# Zio_OLED_Display.net
KiCad netlist of a schematic drawn in EAGLE
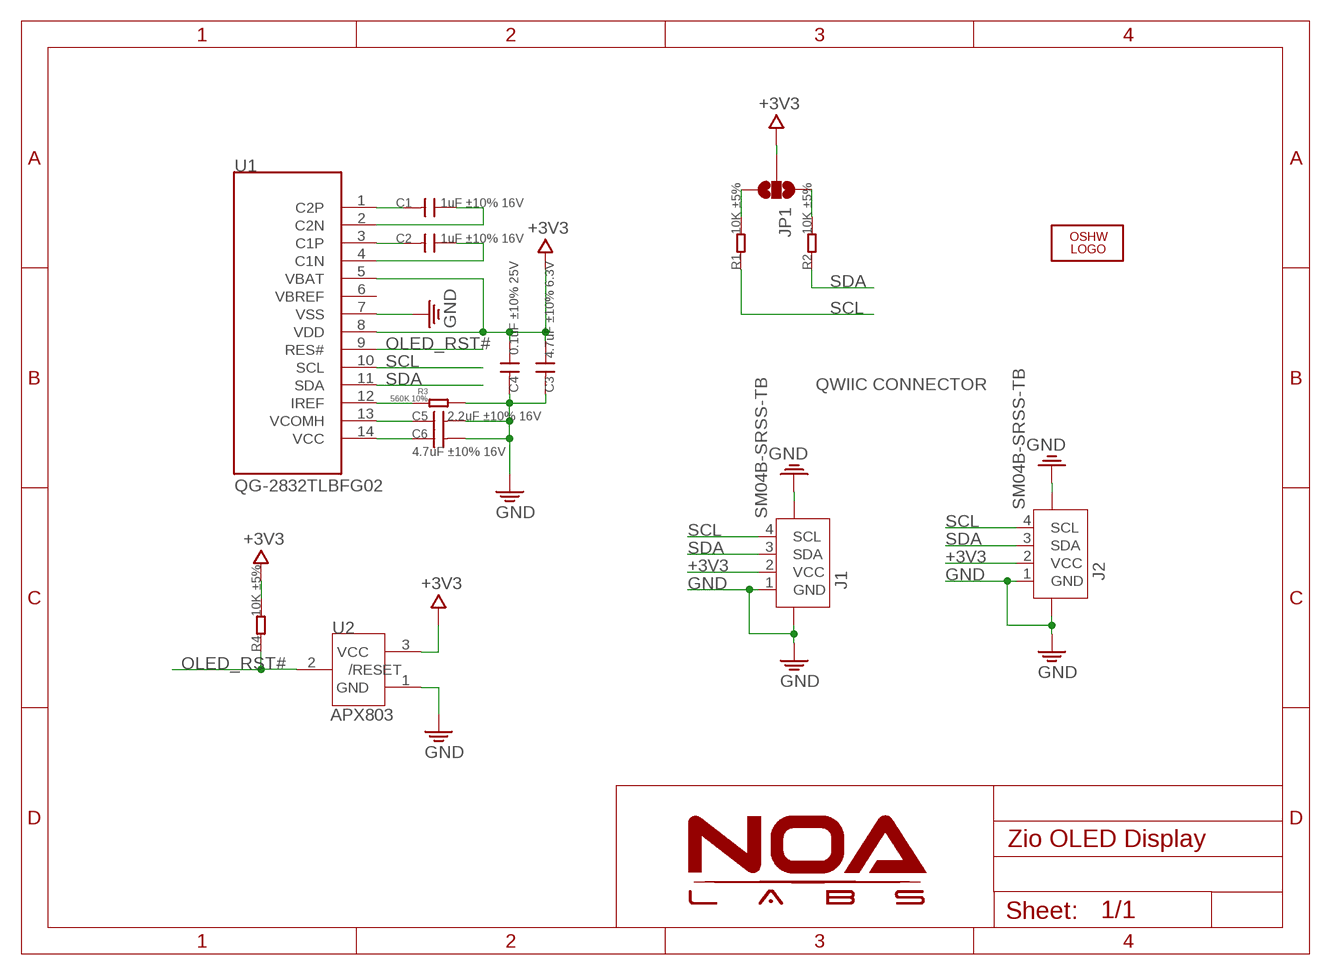
[diagram p0: schematic, sheet 1]

(export (version "E")
  (design (tool "Eeschema 10.0.6"))
  (components
    (comp (ref "C1")
      (value "1uF ±10% 16V")
      (footprint "eagle-import:0603")
      (libsource (lib "eagle-import") (part "C-0603"))
    )
    (comp (ref "C2")
      (value "1uF ±10% 16V")
      (footprint "eagle-import:0603")
      (libsource (lib "eagle-import") (part "C-0603"))
    )
    (comp (ref "C3")
      (value "4.7uF ±10% 6.3V")
      (footprint "eagle-import:0603")
      (libsource (lib "eagle-import") (part "C-0603"))
    )
    (comp (ref "C4")
      (value "0.1uF ±10% 25V")
      (footprint "eagle-import:0603")
      (libsource (lib "eagle-import") (part "C-0603"))
    )
    (comp (ref "C5")
      (value "2.2uF ±10% 16V")
      (footprint "eagle-import:0603")
      (libsource (lib "eagle-import") (part "C-0603"))
    )
    (comp (ref "C6")
      (value "4.7uF ±10% 16V")
      (footprint "eagle-import:0603")
      (libsource (lib "eagle-import") (part "C-0603"))
    )
    (comp (ref "J1")
      (value "SM04B-SRSS-TB")
      (footprint "eagle-import:JST-SH-4P")
      (libsource (lib "eagle-import") (part "JST-SH-4P-1.0"))
    )
    (comp (ref "J2")
      (value "SM04B-SRSS-TB")
      (footprint "eagle-import:JST-SH-4P")
      (libsource (lib "eagle-import") (part "JST-SH-4P-1.0"))
    )
    (comp (ref "JP1")
      (value "JUMPER-SMT_3_2-NC_PASTE_NOCREM")
      (footprint "eagle-import:SMT-JUMPER_3_2-NC_PASTE_SILK_NOCREM")
      (libsource (lib "eagle-import") (part "JUMPER-SMT_3_2-NC_PASTE_NOCREM"))
    )
    (comp (ref "LOGO1")
      (value "LOGO-OSHW-6MILX0070-NT")
      (footprint "eagle-import:OSHW_6X70_NOTEXT")
      (libsource (lib "eagle-import") (part "LOGO-OSHW-6MILX0070-NT"))
    )
    (comp (ref "R1")
      (value "10K ±5%")
      (footprint "eagle-import:0603")
      (libsource (lib "eagle-import") (part "R-0603"))
    )
    (comp (ref "R2")
      (value "10K ±5%")
      (footprint "eagle-import:0603")
      (libsource (lib "eagle-import") (part "R-0603"))
    )
    (comp (ref "R3")
      (value "560K 10%")
      (footprint "eagle-import:0603")
      (libsource (lib "eagle-import") (part "R-0603"))
    )
    (comp (ref "R4")
      (value "10K ±5%")
      (footprint "eagle-import:0603")
      (libsource (lib "eagle-import") (part "R-0603"))
    )
    (comp (ref "U1")
      (value "QG-2832TLBFG02")
      (footprint "eagle-import:OLED-12832")
      (libsource (lib "eagle-import") (part "OLED-12832"))
    )
    (comp (ref "U2")
      (value "APX803")
      (footprint "eagle-import:SOT23")
      (libsource (lib "eagle-import") (part "APX803"))
    )
  )
  (nets
    (net (code "1") (name "+3V3") (class "Default")
      (node (ref "C3") (pin "1") (pinfunction "1_1") (pintype "passive"))
      (node (ref "C4") (pin "1") (pinfunction "1_1") (pintype "passive"))
      (node (ref "J1") (pin "2") (pinfunction "VCC_2") (pintype "bidirectional"))
      (node (ref "J2") (pin "2") (pinfunction "VCC_2") (pintype "bidirectional"))
      (node (ref "JP1") (pin "2") (pinfunction "2_2") (pintype "passive"))
      (node (ref "R4") (pin "2") (pinfunction "2_2") (pintype "passive"))
      (node (ref "U1") (pin "5") (pinfunction "VBAT_5") (pintype "bidirectional"))
      (node (ref "U1") (pin "8") (pinfunction "VDD_8") (pintype "bidirectional"))
      (node (ref "U2") (pin "3") (pinfunction "VCC_3") (pintype "bidirectional"))
    )
    (net (code "2") (name "/OLED_RST#") (class "Default")
      (node (ref "R4") (pin "1") (pinfunction "1_1") (pintype "passive"))
      (node (ref "U1") (pin "9") (pinfunction "RES#_9") (pintype "bidirectional"))
      (node (ref "U2") (pin "2") (pinfunction "/RESET_2") (pintype "bidirectional"))
    )
    (net (code "3") (name "/SCL") (class "Default")
      (node (ref "J1") (pin "4") (pinfunction "SCL_4") (pintype "bidirectional"))
      (node (ref "J2") (pin "4") (pinfunction "SCL_4") (pintype "bidirectional"))
      (node (ref "R1") (pin "1") (pinfunction "1_1") (pintype "passive"))
      (node (ref "U1") (pin "10") (pinfunction "SCL_10") (pintype "bidirectional"))
    )
    (net (code "4") (name "/SDA") (class "Default")
      (node (ref "J1") (pin "3") (pinfunction "SDA_3") (pintype "bidirectional"))
      (node (ref "J2") (pin "3") (pinfunction "SDA_3") (pintype "bidirectional"))
      (node (ref "R2") (pin "1") (pinfunction "1_1") (pintype "passive"))
      (node (ref "U1") (pin "11") (pinfunction "SDA_11") (pintype "bidirectional"))
    )
    (net (code "5") (name "GND") (class "Default")
      (node (ref "C3") (pin "2") (pinfunction "2_2") (pintype "passive"))
      (node (ref "C4") (pin "2") (pinfunction "2_2") (pintype "passive"))
      (node (ref "C5") (pin "2") (pinfunction "2_2") (pintype "passive"))
      (node (ref "C6") (pin "2") (pinfunction "2_2") (pintype "passive"))
      (node (ref "J1") (pin "1") (pinfunction "GND_1") (pintype "bidirectional"))
      (node (ref "J1") (pin "NC1") (pinfunction "5_NC1") (pintype "bidirectional"))
      (node (ref "J1") (pin "NC2") (pinfunction "6_NC2") (pintype "bidirectional"))
      (node (ref "J2") (pin "1") (pinfunction "GND_1") (pintype "bidirectional"))
      (node (ref "J2") (pin "NC1") (pinfunction "5_NC1") (pintype "bidirectional"))
      (node (ref "J2") (pin "NC2") (pinfunction "6_NC2") (pintype "bidirectional"))
      (node (ref "R3") (pin "1") (pinfunction "1_1") (pintype "passive"))
      (node (ref "U1") (pin "7") (pinfunction "VSS_7") (pintype "bidirectional"))
      (node (ref "U2") (pin "1") (pinfunction "GND_1") (pintype "bidirectional"))
    )
    (net (code "6") (name "Net-(JP1-Pad1)") (class "Default")
      (node (ref "JP1") (pin "1") (pinfunction "1_1") (pintype "passive"))
      (node (ref "R2") (pin "2") (pinfunction "2_2") (pintype "passive"))
    )
    (net (code "7") (name "Net-(JP1-Pad3)") (class "Default")
      (node (ref "JP1") (pin "3") (pinfunction "3_3") (pintype "passive"))
      (node (ref "R1") (pin "2") (pinfunction "2_2") (pintype "passive"))
    )
    (net (code "8") (name "Net-(U1-C1N)") (class "Default")
      (node (ref "C2") (pin "1") (pinfunction "1_1") (pintype "passive"))
      (node (ref "U1") (pin "4") (pinfunction "C1N_4") (pintype "bidirectional"))
    )
    (net (code "9") (name "Net-(U1-C1P)") (class "Default")
      (node (ref "C2") (pin "2") (pinfunction "2_2") (pintype "passive"))
      (node (ref "U1") (pin "3") (pinfunction "C1P_3") (pintype "bidirectional"))
    )
    (net (code "10") (name "Net-(U1-C2N)") (class "Default")
      (node (ref "C1") (pin "1") (pinfunction "1_1") (pintype "passive"))
      (node (ref "U1") (pin "2") (pinfunction "C2N_2") (pintype "bidirectional"))
    )
    (net (code "11") (name "Net-(U1-C2P)") (class "Default")
      (node (ref "C1") (pin "2") (pinfunction "2_2") (pintype "passive"))
      (node (ref "U1") (pin "1") (pinfunction "C2P_1") (pintype "bidirectional"))
    )
    (net (code "12") (name "Net-(U1-IREF)") (class "Default")
      (node (ref "R3") (pin "2") (pinfunction "2_2") (pintype "passive"))
      (node (ref "U1") (pin "12") (pinfunction "IREF_12") (pintype "bidirectional"))
    )
    (net (code "13") (name "Net-(U1-VCC)") (class "Default")
      (node (ref "C6") (pin "1") (pinfunction "1_1") (pintype "passive"))
      (node (ref "U1") (pin "14") (pinfunction "VCC_14") (pintype "bidirectional"))
    )
    (net (code "14") (name "Net-(U1-VCOMH)") (class "Default")
      (node (ref "C5") (pin "1") (pinfunction "1_1") (pintype "passive"))
      (node (ref "U1") (pin "13") (pinfunction "VCOMH_13") (pintype "bidirectional"))
    )
    (net (code "15") (name "unconnected-(U1-VBREF-Pad6)") (class "Default")
      (node (ref "U1") (pin "6") (pinfunction "VBREF_6") (pintype "bidirectional"))
    )
  )
)
